# Placa2.net
KiCad netlist of a schematic drawn in Altium Designer
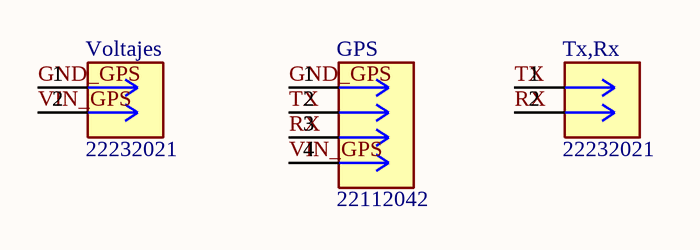
[diagram p0: Placa2.SchDoc]

(export (version "E")
  (design (tool "Eeschema 10.0.6"))
  (components
    (comp (ref "GPS")
      (value "22112042")
      (footprint "CONN_A-6373-04A_MOL")
      (libsource (lib "22112042") (part "22112042"))
    )
    (comp (ref "Tx,Rx")
      (value "22232021")
      (footprint "CONN_A-6373-02A_MOL")
      (description "Connector Header Through Hole 2 position 0.100 (2.54mm)")
      (fields (field (name "MF") "Molex"))
      (libsource (lib "22232021") (part "22232021"))
    )
    (comp (ref "Voltajes")
      (value "22232021")
      (footprint "CONN_A-6373-02A_MOL")
      (description "Connector Header Through Hole 2 position 0.100 (2.54mm)")
      (fields (field (name "MF") "Molex"))
      (libsource (lib "22232021") (part "22232021"))
    )
  )
  (nets
    (net (code "1") (name "/GND_GPS") (class "Default")
      (node (ref "GPS") (pin "1") (pinfunction "1_1") (pintype "passive"))
      (node (ref "Voltajes") (pin "1") (pinfunction "1_1") (pintype "passive"))
    )
    (net (code "2") (name "/RX") (class "Default")
      (node (ref "GPS") (pin "3") (pinfunction "3_3") (pintype "passive"))
      (node (ref "Tx,Rx") (pin "2") (pinfunction "2_2") (pintype "passive"))
    )
    (net (code "3") (name "/TX") (class "Default")
      (node (ref "GPS") (pin "2") (pinfunction "2_2") (pintype "passive"))
      (node (ref "Tx,Rx") (pin "1") (pinfunction "1_1") (pintype "passive"))
    )
    (net (code "4") (name "/VIN_GPS") (class "Default")
      (node (ref "GPS") (pin "4") (pinfunction "4_4") (pintype "passive"))
      (node (ref "Voltajes") (pin "2") (pinfunction "2_2") (pintype "passive"))
    )
  )
)
